# LoRa-GPS.net
KiCad netlist of a schematic drawn in EAGLE
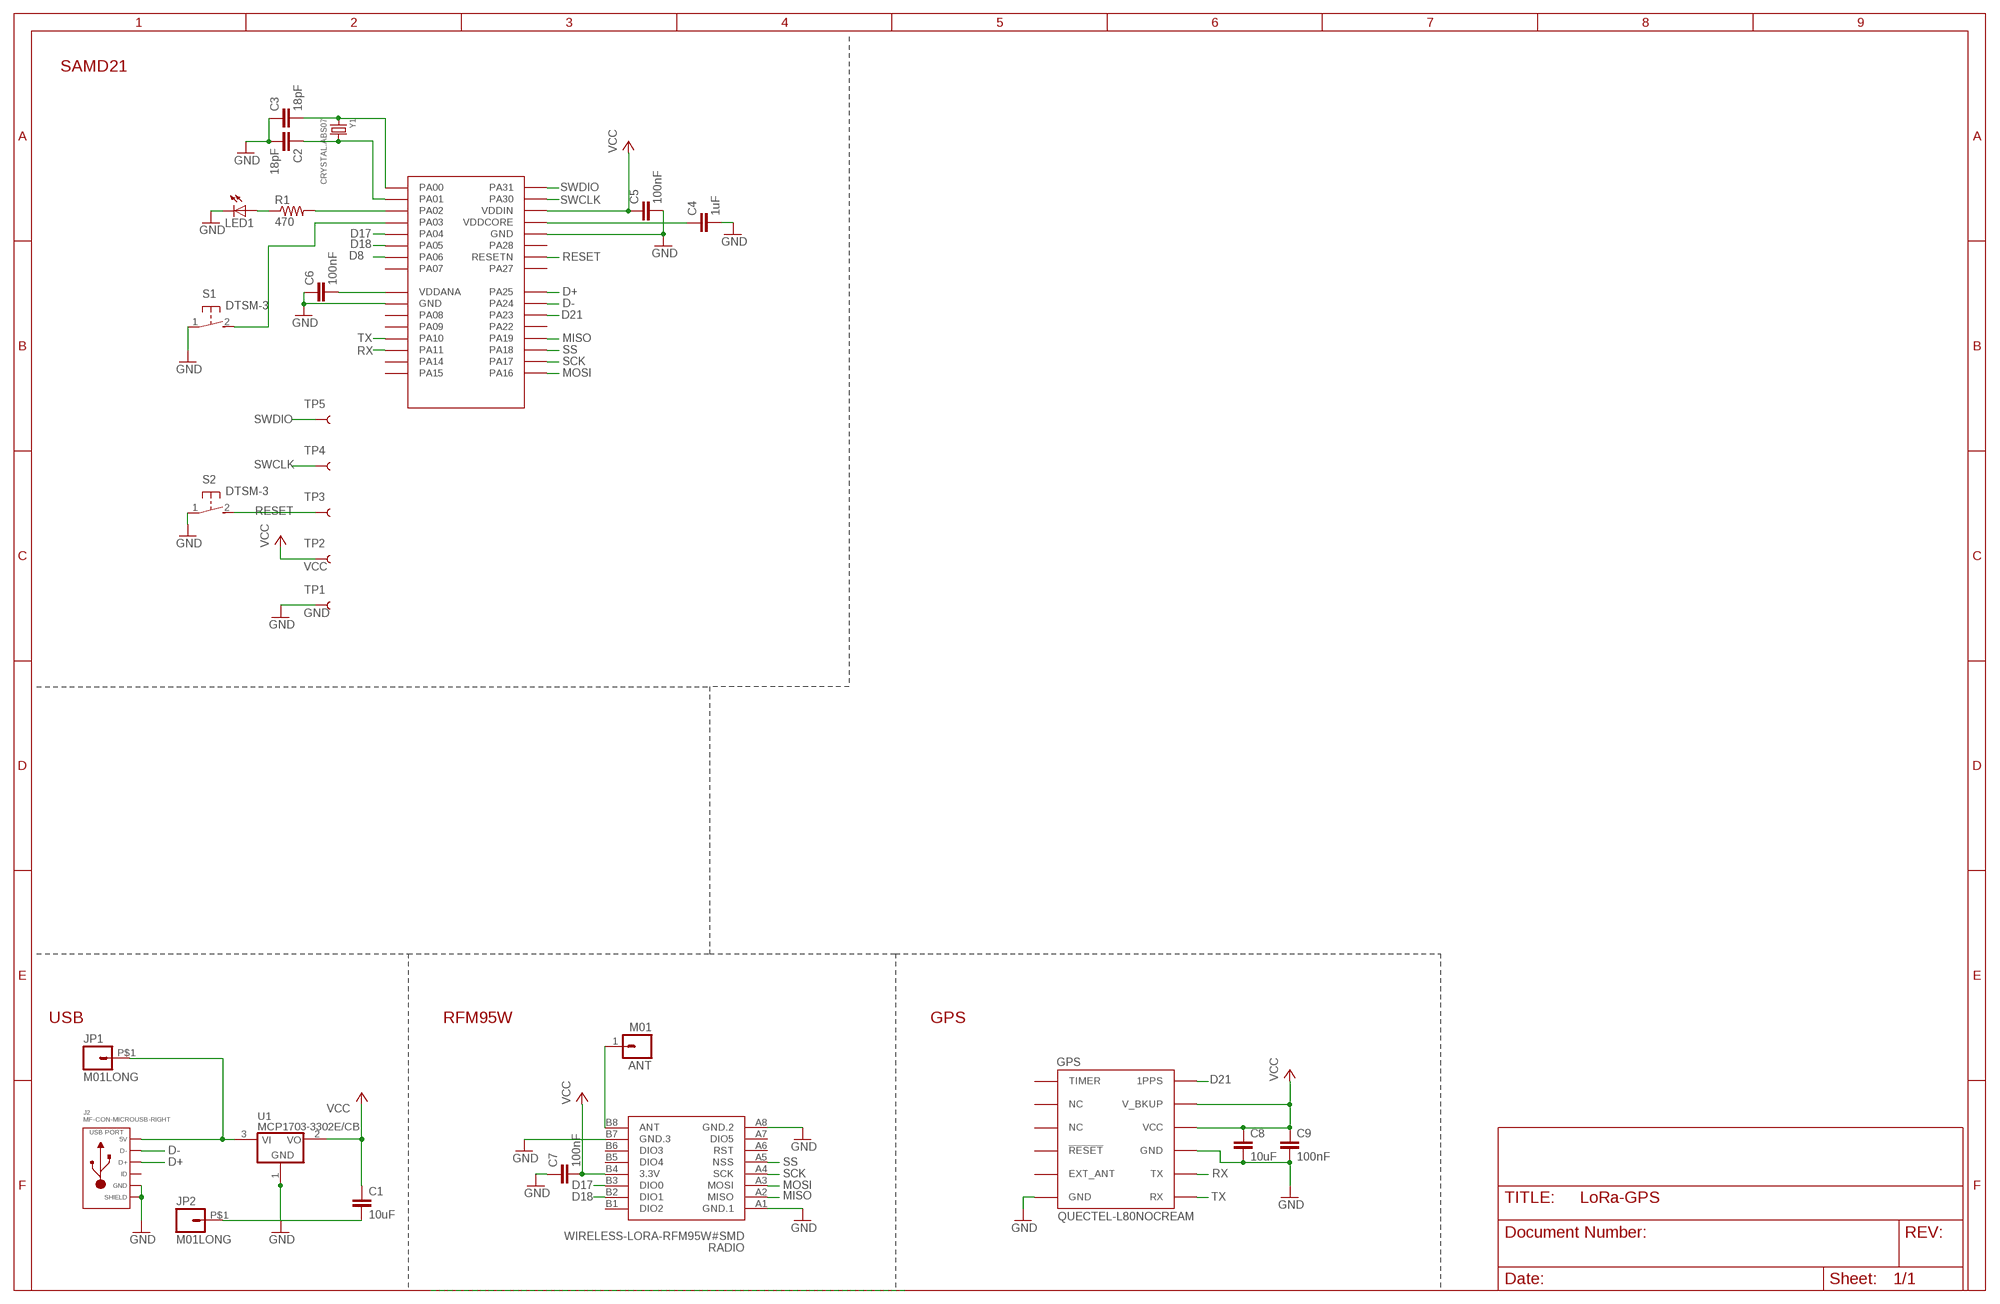
[diagram p0: schematic, sheet 1]

(export (version "E")
  (design (tool "Eeschema 10.0.6"))
  (components
    (comp (ref "ANT")
      (value "M01")
      (footprint "eagle-import:1X01")
      (libsource (lib "eagle-import") (part "M01"))
    )
    (comp (ref "C1")
      (value "10uF")
      (footprint "eagle-import:C0603-THINCREAM")
      (libsource (lib "eagle-import") (part "CAPC0603-THINCREAM"))
    )
    (comp (ref "C2")
      (value "18pF")
      (footprint "eagle-import:C0603-THINCREAM")
      (libsource (lib "eagle-import") (part "CAPC0603-THINCREAM"))
    )
    (comp (ref "C3")
      (value "18pF")
      (footprint "eagle-import:C0603-THINCREAM")
      (libsource (lib "eagle-import") (part "CAPC0603-THINCREAM"))
    )
    (comp (ref "C4")
      (value "1uF")
      (footprint "eagle-import:C0603-THINCREAM")
      (libsource (lib "eagle-import") (part "CAPC0603-THINCREAM"))
    )
    (comp (ref "C5")
      (value "100nF")
      (footprint "eagle-import:C0603-THINCREAM")
      (libsource (lib "eagle-import") (part "CAPC0603-THINCREAM"))
    )
    (comp (ref "C6")
      (value "100nF")
      (footprint "eagle-import:C0603-THINCREAM")
      (libsource (lib "eagle-import") (part "CAPC0603-THINCREAM"))
    )
    (comp (ref "C7")
      (value "100nF")
      (footprint "eagle-import:C0603-THINCREAM")
      (libsource (lib "eagle-import") (part "CAPC0603-THINCREAM"))
    )
    (comp (ref "C8")
      (value "10uF")
      (footprint "eagle-import:C0603-THINCREAM")
      (libsource (lib "eagle-import") (part "CAPC0603-THINCREAM"))
    )
    (comp (ref "C9")
      (value "100nF")
      (footprint "eagle-import:C0603-THINCREAM")
      (libsource (lib "eagle-import") (part "CAPC0603-THINCREAM"))
    )
    (comp (ref "GPS")
      (value "QUECTEL-L80NOCREAM")
      (footprint "eagle-import:QUECTEL-L80-NOCREAM")
      (libsource (lib "eagle-import") (part "QUECTEL-L80NOCREAM"))
    )
    (comp (ref "J2")
      (value "MF-CON-MICROUSB-RIGHT")
      (footprint "eagle-import:MICROUSB-RIGHT")
      (fields (field (name "HOUSEPART") "YES"))
      (libsource (lib "eagle-import") (part "USB_MICRO_RIGHT"))
    )
    (comp (ref "JP1")
      (value "M01LONG")
      (footprint "eagle-import:1X01_LONG")
      (libsource (lib "eagle-import") (part "M01LONG"))
    )
    (comp (ref "JP2")
      (value "M01LONG")
      (footprint "eagle-import:1X01_LONG")
      (libsource (lib "eagle-import") (part "M01LONG"))
    )
    (comp (ref "LED1")
      (value "LEDCHIPLED_0805_THINCREAM")
      (footprint "eagle-import:CHIPLED_0805-THINCREAM")
      (libsource (lib "eagle-import") (part "LEDCHIPLED_0805_THINCREAM"))
    )
    (comp (ref "R1")
      (value "470")
      (footprint "eagle-import:R0603-THINCREAM")
      (libsource (lib "eagle-import") (part "R-USR0603-THINCREAM"))
    )
    (comp (ref "RADIO")
      (value "WIRELESS-LORA-RFM95W#SMD")
      (footprint "eagle-import:WIRELESS-LORA-RFM95W#SMD")
      (libsource (lib "eagle-import") (part "WIRELESS-LORA-RFM95W#SMD"))
    )
    (comp (ref "S1")
      (value "DTSM-3")
      (footprint "eagle-import:DTSM-3")
      (libsource (lib "eagle-import") (part "DTSM-3"))
    )
    (comp (ref "S2")
      (value "DTSM-3")
      (footprint "eagle-import:DTSM-3")
      (libsource (lib "eagle-import") (part "DTSM-3"))
    )
    (comp (ref "SAMD21")
      (value "ATSAMD21E18A-AU")
      (footprint "eagle-import:32-TQFP")
      (libsource (lib "eagle-import") (part "ATSAMD21E18A-AU"))
    )
    (comp (ref "TP1")
      (value "GND")
      (footprint "eagle-import:TP_15TH")
      (libsource (lib "eagle-import") (part "TEST-POINTTP_15TH_THRU"))
    )
    (comp (ref "TP2")
      (value "VCC")
      (footprint "eagle-import:PAD.03X.05")
      (libsource (lib "eagle-import") (part "TEST-POINT3X5"))
    )
    (comp (ref "TP3")
      (value "TEST-POINT3X5")
      (footprint "eagle-import:PAD.03X.05")
      (libsource (lib "eagle-import") (part "TEST-POINT3X5"))
    )
    (comp (ref "TP4")
      (value "TEST-POINT3X5")
      (footprint "eagle-import:PAD.03X.05")
      (libsource (lib "eagle-import") (part "TEST-POINT3X5"))
    )
    (comp (ref "TP5")
      (value "TEST-POINT3X5")
      (footprint "eagle-import:PAD.03X.05")
      (libsource (lib "eagle-import") (part "TEST-POINT3X5"))
    )
    (comp (ref "U1")
      (value "MCP1703-3302E/CB")
      (footprint "eagle-import:SOT23A_MICROCHIP_CB")
      (libsource (lib "eagle-import") (part "MCP170302E/CB-33"))
    )
    (comp (ref "Y1")
      (value "CRYSTAL.ABS07")
      (footprint "eagle-import:ABS07")
      (libsource (lib "eagle-import") (part "CRYSTAL.ABS07"))
    )
  )
  (nets
    (net (code "1") (name "/D+") (class "Default")
      (node (ref "J2") (pin "3") (pinfunction "D+_3") (pintype "bidirectional"))
      (node (ref "SAMD21") (pin "24") (pinfunction "PA25_24") (pintype "bidirectional"))
    )
    (net (code "2") (name "/D-") (class "Default")
      (node (ref "J2") (pin "2") (pinfunction "D-_2") (pintype "bidirectional"))
      (node (ref "SAMD21") (pin "23") (pinfunction "PA24_23") (pintype "bidirectional"))
    )
    (net (code "3") (name "/D8") (class "Default")
      (node (ref "SAMD21") (pin "7") (pinfunction "PA06_7") (pintype "bidirectional"))
    )
    (net (code "4") (name "/D17") (class "Default")
      (node (ref "RADIO") (pin "B3") (pinfunction "DIO0_B3") (pintype "bidirectional"))
      (node (ref "SAMD21") (pin "5") (pinfunction "PA04_5") (pintype "bidirectional"))
    )
    (net (code "5") (name "/D18") (class "Default")
      (node (ref "RADIO") (pin "B2") (pinfunction "DIO1_B2") (pintype "bidirectional"))
      (node (ref "SAMD21") (pin "6") (pinfunction "PA05_6") (pintype "bidirectional"))
    )
    (net (code "6") (name "/D21") (class "Default")
      (node (ref "GPS") (pin "6") (pinfunction "1PPS_6") (pintype "bidirectional"))
      (node (ref "SAMD21") (pin "22") (pinfunction "PA23_22") (pintype "bidirectional"))
    )
    (net (code "7") (name "/MISO") (class "Default")
      (node (ref "RADIO") (pin "A2") (pinfunction "MISO_A2") (pintype "bidirectional"))
      (node (ref "SAMD21") (pin "20") (pinfunction "PA19_20") (pintype "bidirectional"))
    )
    (net (code "8") (name "/MOSI") (class "Default")
      (node (ref "RADIO") (pin "A3") (pinfunction "MOSI_A3") (pintype "bidirectional"))
      (node (ref "SAMD21") (pin "17") (pinfunction "PA16_17") (pintype "bidirectional"))
    )
    (net (code "9") (name "/RESET") (class "Default")
      (node (ref "S2") (pin "2") (pinfunction "2_2") (pintype "passive"))
      (node (ref "SAMD21") (pin "26") (pinfunction "RESETN_26") (pintype "bidirectional"))
      (node (ref "TP3") (pin "P$1") (pinfunction "1_P$1") (pintype "bidirectional"))
    )
    (net (code "10") (name "/RX") (class "Default")
      (node (ref "GPS") (pin "2") (pinfunction "TX_2") (pintype "output"))
      (node (ref "SAMD21") (pin "14") (pinfunction "PA11_14") (pintype "bidirectional"))
    )
    (net (code "11") (name "/SCK") (class "Default")
      (node (ref "RADIO") (pin "A4") (pinfunction "SCK_A4") (pintype "bidirectional"))
      (node (ref "SAMD21") (pin "18") (pinfunction "PA17_18") (pintype "bidirectional"))
    )
    (net (code "12") (name "/SS") (class "Default")
      (node (ref "RADIO") (pin "A5") (pinfunction "NSS_A5") (pintype "bidirectional"))
      (node (ref "SAMD21") (pin "19") (pinfunction "PA18_19") (pintype "bidirectional"))
    )
    (net (code "13") (name "/SWCLK") (class "Default")
      (node (ref "SAMD21") (pin "31") (pinfunction "PA30_31") (pintype "bidirectional"))
      (node (ref "TP4") (pin "P$1") (pinfunction "1_P$1") (pintype "bidirectional"))
    )
    (net (code "14") (name "/SWDIO") (class "Default")
      (node (ref "SAMD21") (pin "32") (pinfunction "PA31_32") (pintype "bidirectional"))
      (node (ref "TP5") (pin "P$1") (pinfunction "1_P$1") (pintype "bidirectional"))
    )
    (net (code "15") (name "/TX") (class "Default")
      (node (ref "GPS") (pin "1") (pinfunction "RX_1") (pintype "input"))
      (node (ref "SAMD21") (pin "13") (pinfunction "PA10_13") (pintype "bidirectional"))
    )
    (net (code "16") (name "GND") (class "Default")
      (node (ref "C1") (pin "2") (pinfunction "2_2") (pintype "passive"))
      (node (ref "C2") (pin "2") (pinfunction "2_2") (pintype "passive"))
      (node (ref "C3") (pin "1") (pinfunction "1_1") (pintype "passive"))
      (node (ref "C4") (pin "2") (pinfunction "2_2") (pintype "passive"))
      (node (ref "C5") (pin "2") (pinfunction "2_2") (pintype "passive"))
      (node (ref "C6") (pin "1") (pinfunction "1_1") (pintype "passive"))
      (node (ref "C7") (pin "1") (pinfunction "1_1") (pintype "passive"))
      (node (ref "C8") (pin "2") (pinfunction "2_2") (pintype "passive"))
      (node (ref "C9") (pin "2") (pinfunction "2_2") (pintype "passive"))
      (node (ref "GPS") (pin "12") (pinfunction "GND_12") (pintype "power_in"))
      (node (ref "GPS") (pin "3") (pinfunction "GND_3") (pintype "power_in"))
      (node (ref "J2") (pin "5") (pinfunction "GND_5") (pintype "power_in"))
      (node (ref "J2") (pin "S1") (pinfunction "SLD_S1") (pintype "power_in"))
      (node (ref "J2") (pin "S2") (pinfunction "SLD_S2") (pintype "power_in"))
      (node (ref "J2") (pin "S3") (pinfunction "SLD_S3") (pintype "power_in"))
      (node (ref "J2") (pin "S4") (pinfunction "SLD_S4") (pintype "power_in"))
      (node (ref "JP2") (pin "P$1") (pinfunction "1_P$1") (pintype "passive"))
      (node (ref "LED1") (pin "C") (pinfunction "C_C") (pintype "passive"))
      (node (ref "RADIO") (pin "A1") (pinfunction "GND.1_A1") (pintype "power_in"))
      (node (ref "RADIO") (pin "A8") (pinfunction "GND.2_A8") (pintype "power_in"))
      (node (ref "RADIO") (pin "B7") (pinfunction "GND.3_B7") (pintype "power_in"))
      (node (ref "S1") (pin "1") (pinfunction "1_1") (pintype "passive"))
      (node (ref "S2") (pin "1") (pinfunction "1_1") (pintype "passive"))
      (node (ref "SAMD21") (pin "10") (pinfunction "GND_10") (pintype "bidirectional"))
      (node (ref "SAMD21") (pin "28") (pinfunction "GND_28") (pintype "bidirectional"))
      (node (ref "TP1") (pin "P$1") (pinfunction "1_P$1") (pintype "bidirectional"))
      (node (ref "U1") (pin "1") (pinfunction "GND_1") (pintype "power_in"))
    )
    (net (code "17") (name "Net-(J2-5V)") (class "Default")
      (node (ref "J2") (pin "1") (pinfunction "5V_1") (pintype "power_in"))
      (node (ref "JP1") (pin "P$1") (pinfunction "1_P$1") (pintype "passive"))
      (node (ref "U1") (pin "3") (pinfunction "VI_3") (pintype "power_in"))
    )
    (net (code "18") (name "Net-(LED1-PadA)") (class "Default")
      (node (ref "LED1") (pin "A") (pinfunction "A_A") (pintype "passive"))
      (node (ref "R1") (pin "1") (pinfunction "1_1") (pintype "passive"))
    )
    (net (code "19") (name "Net-(RADIO-ANT)") (class "Default")
      (node (ref "ANT") (pin "1") (pinfunction "1_1") (pintype "passive"))
      (node (ref "RADIO") (pin "B8") (pinfunction "ANT_B8") (pintype "passive"))
    )
    (net (code "20") (name "Net-(SAMD21-PA00)") (class "Default")
      (node (ref "C3") (pin "2") (pinfunction "2_2") (pintype "passive"))
      (node (ref "SAMD21") (pin "1") (pinfunction "PA00_1") (pintype "bidirectional"))
      (node (ref "Y1") (pin "1") (pinfunction "1_1") (pintype "passive"))
    )
    (net (code "21") (name "Net-(SAMD21-PA01)") (class "Default")
      (node (ref "C2") (pin "1") (pinfunction "1_1") (pintype "passive"))
      (node (ref "SAMD21") (pin "2") (pinfunction "PA01_2") (pintype "bidirectional"))
      (node (ref "Y1") (pin "2") (pinfunction "2_2") (pintype "passive"))
    )
    (net (code "22") (name "Net-(SAMD21-PA02)") (class "Default")
      (node (ref "R1") (pin "2") (pinfunction "2_2") (pintype "passive"))
      (node (ref "SAMD21") (pin "3") (pinfunction "PA02_3") (pintype "bidirectional"))
    )
    (net (code "23") (name "Net-(SAMD21-PA03)") (class "Default")
      (node (ref "S1") (pin "2") (pinfunction "2_2") (pintype "passive"))
      (node (ref "SAMD21") (pin "4") (pinfunction "PA03_4") (pintype "bidirectional"))
    )
    (net (code "24") (name "Net-(SAMD21-VDDANA)") (class "Default")
      (node (ref "C6") (pin "2") (pinfunction "2_2") (pintype "passive"))
      (node (ref "SAMD21") (pin "9") (pinfunction "VDDANA_9") (pintype "bidirectional"))
    )
    (net (code "25") (name "Net-(SAMD21-VDDCORE)") (class "Default")
      (node (ref "C4") (pin "1") (pinfunction "1_1") (pintype "passive"))
      (node (ref "SAMD21") (pin "29") (pinfunction "VDDCORE_29") (pintype "bidirectional"))
    )
    (net (code "26") (name "VCC") (class "Default")
      (node (ref "C1") (pin "1") (pinfunction "1_1") (pintype "passive"))
      (node (ref "C5") (pin "1") (pinfunction "1_1") (pintype "passive"))
      (node (ref "C7") (pin "2") (pinfunction "2_2") (pintype "passive"))
      (node (ref "C8") (pin "1") (pinfunction "1_1") (pintype "passive"))
      (node (ref "C9") (pin "1") (pinfunction "1_1") (pintype "passive"))
      (node (ref "GPS") (pin "4") (pinfunction "VCC_4") (pintype "power_in"))
      (node (ref "GPS") (pin "5") (pinfunction "V_BKUP_5") (pintype "power_in"))
      (node (ref "RADIO") (pin "B4") (pinfunction "3.3V_B4") (pintype "power_in"))
      (node (ref "SAMD21") (pin "30") (pinfunction "VDDIN_30") (pintype "bidirectional"))
      (node (ref "TP2") (pin "P$1") (pinfunction "1_P$1") (pintype "bidirectional"))
      (node (ref "U1") (pin "2") (pinfunction "VO_2") (pintype "passive"))
    )
    (net (code "27") (name "unconnected-(GPS-EXT_ANT-Pad11)") (class "Default")
      (node (ref "GPS") (pin "11") (pinfunction "EXT_ANT_11") (pintype "bidirectional"))
    )
    (net (code "28") (name "unconnected-(GPS-NC-Pad8)") (class "Default")
      (node (ref "GPS") (pin "8") (pinfunction "NC_8") (pintype "no_connect"))
    )
    (net (code "29") (name "unconnected-(GPS-NC-Pad9)") (class "Default")
      (node (ref "GPS") (pin "9") (pinfunction "NC_9") (pintype "no_connect"))
    )
    (net (code "30") (name "unconnected-(GPS-TIMER-Pad7)") (class "Default")
      (node (ref "GPS") (pin "7") (pinfunction "TIMER_7") (pintype "bidirectional"))
    )
    (net (code "31") (name "unconnected-(GPS-~{RESET}-Pad10)") (class "Default")
      (node (ref "GPS") (pin "10") (pinfunction "~{RESET}_10") (pintype "input"))
    )
    (net (code "32") (name "unconnected-(J2-ID-Pad4)") (class "Default")
      (node (ref "J2") (pin "4") (pinfunction "ID_4") (pintype "bidirectional"))
    )
    (net (code "33") (name "unconnected-(RADIO-DIO2-PadB1)") (class "Default")
      (node (ref "RADIO") (pin "B1") (pinfunction "DIO2_B1") (pintype "bidirectional"))
    )
    (net (code "34") (name "unconnected-(RADIO-DIO3-PadB6)") (class "Default")
      (node (ref "RADIO") (pin "B6") (pinfunction "DIO3_B6") (pintype "bidirectional"))
    )
    (net (code "35") (name "unconnected-(RADIO-DIO4-PadB5)") (class "Default")
      (node (ref "RADIO") (pin "B5") (pinfunction "DIO4_B5") (pintype "bidirectional"))
    )
    (net (code "36") (name "unconnected-(RADIO-DIO5-PadA7)") (class "Default")
      (node (ref "RADIO") (pin "A7") (pinfunction "DIO5_A7") (pintype "bidirectional"))
    )
    (net (code "37") (name "unconnected-(RADIO-RST-PadA6)") (class "Default")
      (node (ref "RADIO") (pin "A6") (pinfunction "RST_A6") (pintype "bidirectional"))
    )
    (net (code "38") (name "unconnected-(SAMD21-PA07-Pad8)") (class "Default")
      (node (ref "SAMD21") (pin "8") (pinfunction "PA07_8") (pintype "bidirectional"))
    )
    (net (code "39") (name "unconnected-(SAMD21-PA08-Pad11)") (class "Default")
      (node (ref "SAMD21") (pin "11") (pinfunction "PA08_11") (pintype "bidirectional"))
    )
    (net (code "40") (name "unconnected-(SAMD21-PA09-Pad12)") (class "Default")
      (node (ref "SAMD21") (pin "12") (pinfunction "PA09_12") (pintype "bidirectional"))
    )
    (net (code "41") (name "unconnected-(SAMD21-PA14-Pad15)") (class "Default")
      (node (ref "SAMD21") (pin "15") (pinfunction "PA14_15") (pintype "bidirectional"))
    )
    (net (code "42") (name "unconnected-(SAMD21-PA15-Pad16)") (class "Default")
      (node (ref "SAMD21") (pin "16") (pinfunction "PA15_16") (pintype "bidirectional"))
    )
    (net (code "43") (name "unconnected-(SAMD21-PA22-Pad21)") (class "Default")
      (node (ref "SAMD21") (pin "21") (pinfunction "PA22_21") (pintype "bidirectional"))
    )
    (net (code "44") (name "unconnected-(SAMD21-PA27-Pad25)") (class "Default")
      (node (ref "SAMD21") (pin "25") (pinfunction "PA27_25") (pintype "bidirectional"))
    )
    (net (code "45") (name "unconnected-(SAMD21-PA28-Pad27)") (class "Default")
      (node (ref "SAMD21") (pin "27") (pinfunction "PA28_27") (pintype "bidirectional"))
    )
  )
)
